# p08_boot.net
KiCad netlist of a schematic drawn in Altium Designer
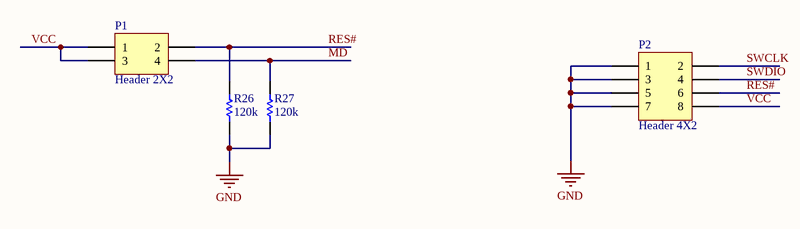
[diagram p0: p08_boot.SchDoc]

(export (version "E")
  (design (tool "Eeschema 10.0.6"))
  (components
    (comp (ref "P1")
      (value "Header 2X2")
      (footprint "HDR2X2")
      (description "Header, 2-Pin, Dual row")
      (fields (field (name "PUBLISHER") "Altium Limited"))
      (libsource (lib "Miscellaneous Connectors") (part "Header 2X2"))
    )
    (comp (ref "P2")
      (value "Header 4X2")
      (footprint "HDR2X4")
      (description "Header, 4-Pin, Dual row")
      (fields (field (name "PUBLISHER") "Altium Limited"))
      (libsource (lib "Miscellaneous Connectors") (part "Header 4X2"))
    )
    (comp (ref "R26")
      (value "120k")
      (footprint "6-0805_M")
      (description "Resistor")
      (fields (field (name "Comment") "Res1") (field (name "PUBLISHER") "Altium Limited"))
      (libsource (lib "Miscellaneous Devices") (part "Res1"))
    )
    (comp (ref "R27")
      (value "120k")
      (footprint "6-0805_M")
      (description "Resistor")
      (fields (field (name "Comment") "Res1") (field (name "PUBLISHER") "Altium Limited"))
      (libsource (lib "Miscellaneous Devices") (part "Res1"))
    )
  )
  (nets
    (net (code "1") (name "/MD") (class "Default")
      (node (ref "P1") (pin "4") (pinfunction "4_4") (pintype "passive"))
      (node (ref "R27") (pin "1") (pinfunction "1_1") (pintype "passive"))
    )
    (net (code "2") (name "/RES#") (class "Default")
      (node (ref "P1") (pin "2") (pinfunction "2_2") (pintype "passive"))
      (node (ref "P2") (pin "6") (pinfunction "6_6") (pintype "passive"))
      (node (ref "R26") (pin "1") (pinfunction "1_1") (pintype "passive"))
    )
    (net (code "3") (name "/SWCLK") (class "Default")
      (node (ref "P2") (pin "2") (pinfunction "2_2") (pintype "passive"))
    )
    (net (code "4") (name "/SWDIO") (class "Default")
      (node (ref "P2") (pin "4") (pinfunction "4_4") (pintype "passive"))
    )
    (net (code "5") (name "/VCC") (class "Default")
      (node (ref "P1") (pin "1") (pinfunction "1_1") (pintype "passive"))
      (node (ref "P1") (pin "3") (pinfunction "3_3") (pintype "passive"))
      (node (ref "P2") (pin "8") (pinfunction "8_8") (pintype "passive"))
    )
    (net (code "6") (name "GND") (class "Default")
      (node (ref "P2") (pin "1") (pinfunction "1_1") (pintype "passive"))
      (node (ref "P2") (pin "3") (pinfunction "3_3") (pintype "passive"))
      (node (ref "P2") (pin "5") (pinfunction "5_5") (pintype "passive"))
      (node (ref "P2") (pin "7") (pinfunction "7_7") (pintype "passive"))
      (node (ref "R26") (pin "2") (pinfunction "2_2") (pintype "passive"))
      (node (ref "R27") (pin "2") (pinfunction "2_2") (pintype "passive"))
    )
  )
)
